# Adafruit_NeoPixel_8_Stick_v2.net
KiCad netlist of a schematic drawn in EAGLE
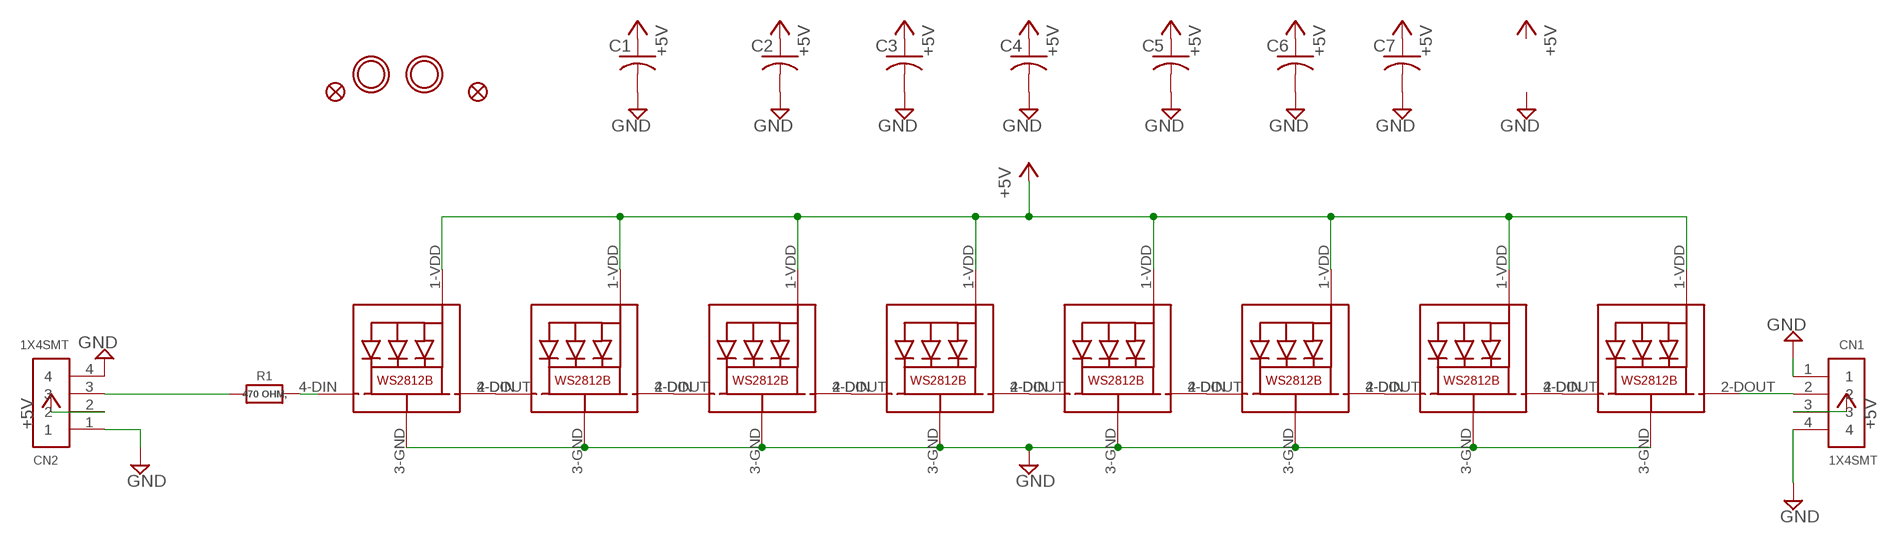
[diagram p0: schematic, sheet 1]

(export (version "E")
  (design (tool "Eeschema 10.0.6"))
  (components
    (comp (ref "C1")
      (value "C-USC0805K")
      (footprint "eagle-import:C0805K")
      (libsource (lib "eagle-import") (part "C-USC0805K"))
    )
    (comp (ref "C2")
      (value "C-USC0805K")
      (footprint "eagle-import:C0805K")
      (libsource (lib "eagle-import") (part "C-USC0805K"))
    )
    (comp (ref "C3")
      (value "C-USC0805K")
      (footprint "eagle-import:C0805K")
      (libsource (lib "eagle-import") (part "C-USC0805K"))
    )
    (comp (ref "C4")
      (value "C-USC0805K")
      (footprint "eagle-import:C0805K")
      (libsource (lib "eagle-import") (part "C-USC0805K"))
    )
    (comp (ref "C5")
      (value "C-USC0805K")
      (footprint "eagle-import:C0805K")
      (libsource (lib "eagle-import") (part "C-USC0805K"))
    )
    (comp (ref "C6")
      (value "C-USC0805K")
      (footprint "eagle-import:C0805K")
      (libsource (lib "eagle-import") (part "C-USC0805K"))
    )
    (comp (ref "C7")
      (value "C-USC0805K")
      (footprint "eagle-import:C0805K")
      (libsource (lib "eagle-import") (part "C-USC0805K"))
    )
    (comp (ref "CN1")
      (value "1X4SMT")
      (footprint "eagle-import:1X4-SMT")
      (libsource (lib "eagle-import") (part "1X4SMT"))
    )
    (comp (ref "CN2")
      (value "1X4SMT")
      (footprint "eagle-import:1X4-SMT")
      (libsource (lib "eagle-import") (part "1X4SMT"))
    )
    (comp (ref "FID1")
      (value "FIDUCIAL\"\"")
      (footprint "eagle-import:FIDUCIAL_1MM")
      (libsource (lib "eagle-import") (part "FIDUCIAL{dblquote}{dblquote}"))
    )
    (comp (ref "FID3")
      (value "FIDUCIAL\"\"")
      (footprint "eagle-import:FIDUCIAL_1MM")
      (libsource (lib "eagle-import") (part "FIDUCIAL{dblquote}{dblquote}"))
    )
    (comp (ref "LED1")
      (value "WS2812B5050")
      (footprint "eagle-import:WS2812B")
      (libsource (lib "eagle-import") (part "WS2812B5050"))
    )
    (comp (ref "LED2")
      (value "WS2812B5050")
      (footprint "eagle-import:WS2812B")
      (libsource (lib "eagle-import") (part "WS2812B5050"))
    )
    (comp (ref "LED3")
      (value "WS2812B5050")
      (footprint "eagle-import:WS2812B")
      (libsource (lib "eagle-import") (part "WS2812B5050"))
    )
    (comp (ref "LED4")
      (value "WS2812B5050")
      (footprint "eagle-import:WS2812B")
      (libsource (lib "eagle-import") (part "WS2812B5050"))
    )
    (comp (ref "LED5")
      (value "WS2812B5050")
      (footprint "eagle-import:WS2812B")
      (libsource (lib "eagle-import") (part "WS2812B5050"))
    )
    (comp (ref "LED6")
      (value "WS2812B5050")
      (footprint "eagle-import:WS2812B")
      (libsource (lib "eagle-import") (part "WS2812B5050"))
    )
    (comp (ref "LED7")
      (value "WS2812B5050")
      (footprint "eagle-import:WS2812B")
      (libsource (lib "eagle-import") (part "WS2812B5050"))
    )
    (comp (ref "LED8")
      (value "WS2812B5050")
      (footprint "eagle-import:WS2812B")
      (libsource (lib "eagle-import") (part "WS2812B5050"))
    )
    (comp (ref "R1")
      (value "470 OHM,")
      (footprint "eagle-import:_0805MP")
      (libsource (lib "eagle-import") (part "RESISTOR_0805MP"))
    )
    (comp (ref "U$2")
      (value "MOUNTINGHOLE2.0")
      (footprint "eagle-import:MOUNTINGHOLE_2.0_PLATED")
      (libsource (lib "eagle-import") (part "MOUNTINGHOLE2.0"))
    )
    (comp (ref "U$3")
      (value "MOUNTINGHOLE2.0")
      (footprint "eagle-import:MOUNTINGHOLE_2.0_PLATED")
      (libsource (lib "eagle-import") (part "MOUNTINGHOLE2.0"))
    )
  )
  (nets
    (net (code "1") (name "+5V") (class "Default")
      (node (ref "C1") (pin "1") (pinfunction "1_1") (pintype "passive"))
      (node (ref "C2") (pin "1") (pinfunction "1_1") (pintype "passive"))
      (node (ref "C3") (pin "1") (pinfunction "1_1") (pintype "passive"))
      (node (ref "C4") (pin "1") (pinfunction "1_1") (pintype "passive"))
      (node (ref "C5") (pin "1") (pinfunction "1_1") (pintype "passive"))
      (node (ref "C6") (pin "1") (pinfunction "1_1") (pintype "passive"))
      (node (ref "C7") (pin "1") (pinfunction "1_1") (pintype "passive"))
      (node (ref "CN1") (pin "3") (pinfunction "3_3") (pintype "bidirectional"))
      (node (ref "CN2") (pin "2") (pinfunction "2_2") (pintype "bidirectional"))
      (node (ref "LED1") (pin "1-VDD") (pinfunction "VDD_1-VDD") (pintype "power_in"))
      (node (ref "LED2") (pin "1-VDD") (pinfunction "VDD_1-VDD") (pintype "power_in"))
      (node (ref "LED3") (pin "1-VDD") (pinfunction "VDD_1-VDD") (pintype "power_in"))
      (node (ref "LED4") (pin "1-VDD") (pinfunction "VDD_1-VDD") (pintype "power_in"))
      (node (ref "LED5") (pin "1-VDD") (pinfunction "VDD_1-VDD") (pintype "power_in"))
      (node (ref "LED6") (pin "1-VDD") (pinfunction "VDD_1-VDD") (pintype "power_in"))
      (node (ref "LED7") (pin "1-VDD") (pinfunction "VDD_1-VDD") (pintype "power_in"))
      (node (ref "LED8") (pin "1-VDD") (pinfunction "VDD_1-VDD") (pintype "power_in"))
    )
    (net (code "2") (name "GND") (class "Default")
      (node (ref "C1") (pin "2") (pinfunction "2_2") (pintype "passive"))
      (node (ref "C2") (pin "2") (pinfunction "2_2") (pintype "passive"))
      (node (ref "C3") (pin "2") (pinfunction "2_2") (pintype "passive"))
      (node (ref "C4") (pin "2") (pinfunction "2_2") (pintype "passive"))
      (node (ref "C5") (pin "2") (pinfunction "2_2") (pintype "passive"))
      (node (ref "C6") (pin "2") (pinfunction "2_2") (pintype "passive"))
      (node (ref "C7") (pin "2") (pinfunction "2_2") (pintype "passive"))
      (node (ref "CN1") (pin "1") (pinfunction "1_1") (pintype "bidirectional"))
      (node (ref "CN1") (pin "4") (pinfunction "4_4") (pintype "bidirectional"))
      (node (ref "CN2") (pin "1") (pinfunction "1_1") (pintype "bidirectional"))
      (node (ref "CN2") (pin "4") (pinfunction "4_4") (pintype "bidirectional"))
      (node (ref "LED1") (pin "3-GND") (pinfunction "GND_3-GND") (pintype "power_in"))
      (node (ref "LED2") (pin "3-GND") (pinfunction "GND_3-GND") (pintype "power_in"))
      (node (ref "LED3") (pin "3-GND") (pinfunction "GND_3-GND") (pintype "power_in"))
      (node (ref "LED4") (pin "3-GND") (pinfunction "GND_3-GND") (pintype "power_in"))
      (node (ref "LED5") (pin "3-GND") (pinfunction "GND_3-GND") (pintype "power_in"))
      (node (ref "LED6") (pin "3-GND") (pinfunction "GND_3-GND") (pintype "power_in"))
      (node (ref "LED7") (pin "3-GND") (pinfunction "GND_3-GND") (pintype "power_in"))
      (node (ref "LED8") (pin "3-GND") (pinfunction "GND_3-GND") (pintype "power_in"))
    )
    (net (code "3") (name "Net-(CN2-Pad3)") (class "Default")
      (node (ref "CN2") (pin "3") (pinfunction "3_3") (pintype "bidirectional"))
      (node (ref "R1") (pin "1") (pinfunction "1_1") (pintype "passive"))
    )
    (net (code "4") (name "Net-(LED1-DI)") (class "Default")
      (node (ref "LED1") (pin "4-DIN") (pinfunction "DI_4-DIN") (pintype "input"))
      (node (ref "R1") (pin "2") (pinfunction "2_2") (pintype "passive"))
    )
    (net (code "5") (name "Net-(LED1-DO)") (class "Default")
      (node (ref "LED1") (pin "2-DOUT") (pinfunction "DO_2-DOUT") (pintype "output"))
      (node (ref "LED2") (pin "4-DIN") (pinfunction "DI_4-DIN") (pintype "input"))
    )
    (net (code "6") (name "Net-(LED2-DO)") (class "Default")
      (node (ref "LED2") (pin "2-DOUT") (pinfunction "DO_2-DOUT") (pintype "output"))
      (node (ref "LED3") (pin "4-DIN") (pinfunction "DI_4-DIN") (pintype "input"))
    )
    (net (code "7") (name "Net-(LED3-DO)") (class "Default")
      (node (ref "LED3") (pin "2-DOUT") (pinfunction "DO_2-DOUT") (pintype "output"))
      (node (ref "LED4") (pin "4-DIN") (pinfunction "DI_4-DIN") (pintype "input"))
    )
    (net (code "8") (name "Net-(LED4-DO)") (class "Default")
      (node (ref "LED4") (pin "2-DOUT") (pinfunction "DO_2-DOUT") (pintype "output"))
      (node (ref "LED5") (pin "4-DIN") (pinfunction "DI_4-DIN") (pintype "input"))
    )
    (net (code "9") (name "Net-(LED5-DO)") (class "Default")
      (node (ref "LED5") (pin "2-DOUT") (pinfunction "DO_2-DOUT") (pintype "output"))
      (node (ref "LED6") (pin "4-DIN") (pinfunction "DI_4-DIN") (pintype "input"))
    )
    (net (code "10") (name "Net-(LED6-DO)") (class "Default")
      (node (ref "LED6") (pin "2-DOUT") (pinfunction "DO_2-DOUT") (pintype "output"))
      (node (ref "LED7") (pin "4-DIN") (pinfunction "DI_4-DIN") (pintype "input"))
    )
    (net (code "11") (name "Net-(LED7-DO)") (class "Default")
      (node (ref "LED7") (pin "2-DOUT") (pinfunction "DO_2-DOUT") (pintype "output"))
      (node (ref "LED8") (pin "4-DIN") (pinfunction "DI_4-DIN") (pintype "input"))
    )
    (net (code "12") (name "Net-(LED8-DO)") (class "Default")
      (node (ref "CN1") (pin "2") (pinfunction "2_2") (pintype "bidirectional"))
      (node (ref "LED8") (pin "2-DOUT") (pinfunction "DO_2-DOUT") (pintype "output"))
    )
  )
)
